# Ethernet.net
KiCad netlist of a schematic drawn in Altium Designer
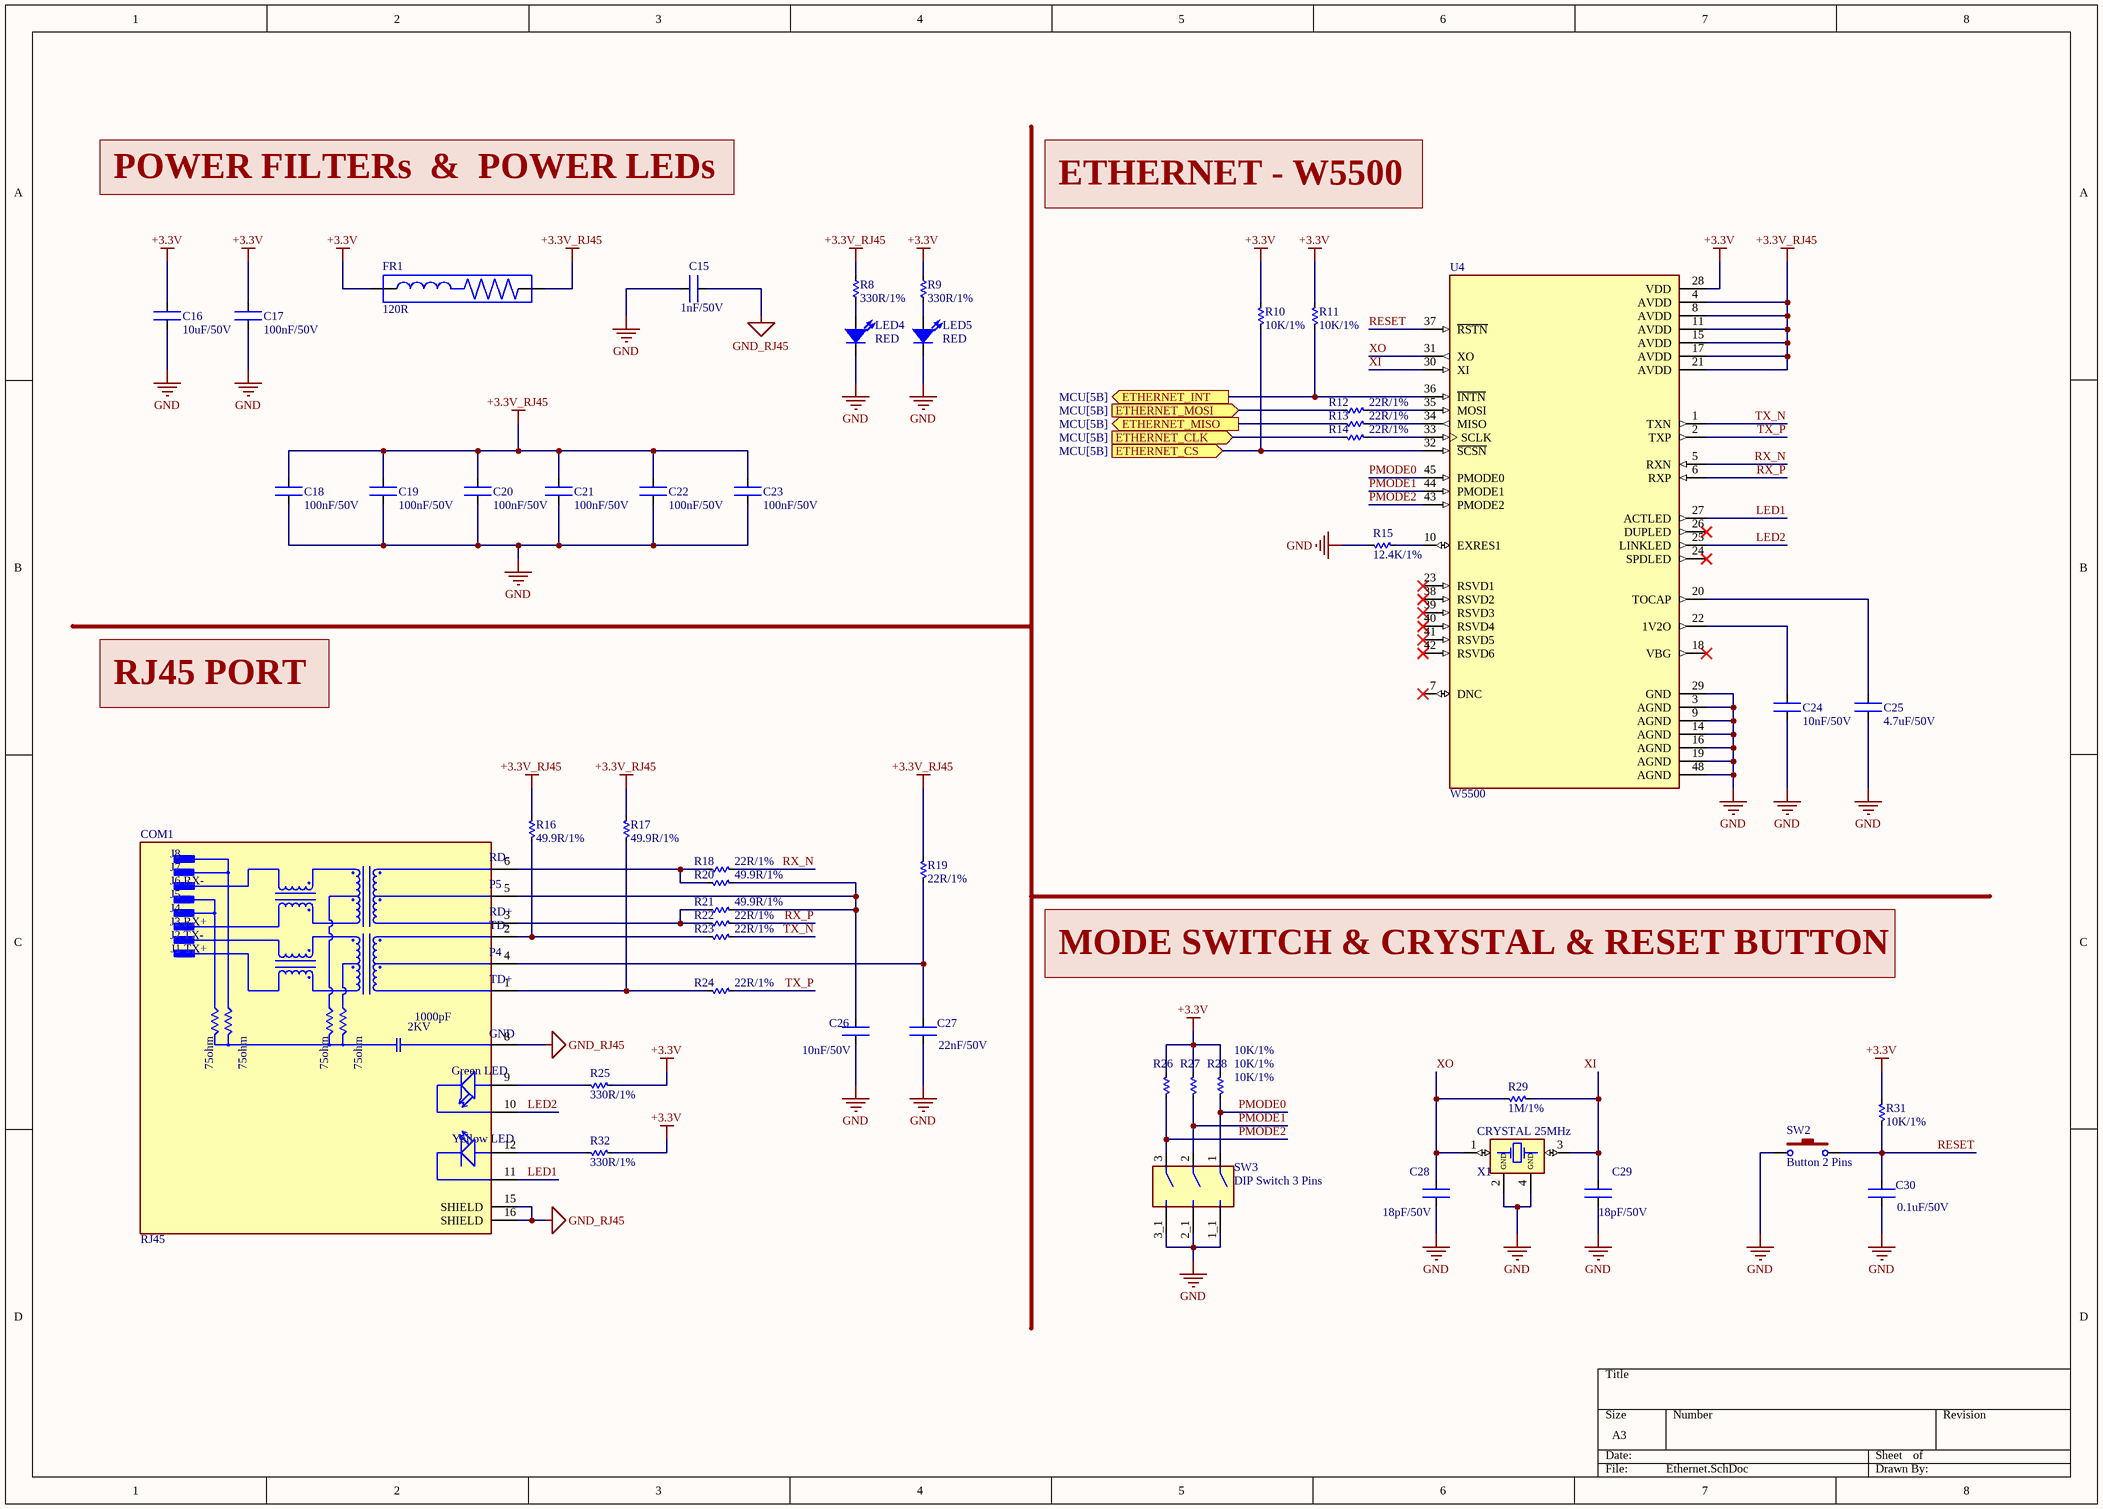
[diagram p0: Ethernet.SchDoc]

(export (version "E")
  (design (tool "Eeschema 10.0.6"))
  (components
    (comp (ref "C15")
      (value "1nF/50V")
      (footprint "CAP - 0603")
      (description "CAPACITOR SMD - KEMET")
      (libsource (lib "NewLibrary") (part "CAPACITOR"))
    )
    (comp (ref "C16")
      (value "10uF/50V")
      (footprint "CAP - 0603")
      (description "CAPACITOR SMD - KEMET")
      (libsource (lib "NewLibrary") (part "CAPACITOR"))
    )
    (comp (ref "C17")
      (value "100nF/50V")
      (footprint "CAP - 0603")
      (description "CAPACITOR SMD - KEMET")
      (libsource (lib "NewLibrary") (part "CAPACITOR"))
    )
    (comp (ref "C18")
      (value "100nF/50V")
      (footprint "CAP - 0603")
      (description "CAPACITOR SMD - KEMET")
      (libsource (lib "NewLibrary") (part "CAPACITOR"))
    )
    (comp (ref "C19")
      (value "100nF/50V")
      (footprint "CAP - 0603")
      (description "CAPACITOR SMD - KEMET")
      (libsource (lib "NewLibrary") (part "CAPACITOR"))
    )
    (comp (ref "C20")
      (value "100nF/50V")
      (footprint "CAP - 0603")
      (description "CAPACITOR SMD - KEMET")
      (libsource (lib "NewLibrary") (part "CAPACITOR"))
    )
    (comp (ref "C21")
      (value "100nF/50V")
      (footprint "CAP - 0603")
      (description "CAPACITOR SMD - KEMET")
      (libsource (lib "NewLibrary") (part "CAPACITOR"))
    )
    (comp (ref "C22")
      (value "100nF/50V")
      (footprint "CAP - 0603")
      (description "CAPACITOR SMD - KEMET")
      (libsource (lib "NewLibrary") (part "CAPACITOR"))
    )
    (comp (ref "C23")
      (value "100nF/50V")
      (footprint "CAP - 0603")
      (description "CAPACITOR SMD - KEMET")
      (libsource (lib "NewLibrary") (part "CAPACITOR"))
    )
    (comp (ref "C24")
      (value "10nF/50V")
      (footprint "CAP - 0603")
      (description "CAPACITOR SMD - KEMET")
      (libsource (lib "NewLibrary") (part "CAPACITOR"))
    )
    (comp (ref "C25")
      (value "4.7uF/50V")
      (footprint "CAP - 0603")
      (description "CAPACITOR SMD - KEMET")
      (libsource (lib "NewLibrary") (part "CAPACITOR"))
    )
    (comp (ref "C26")
      (value "10nF/50V")
      (footprint "CAP - 0603")
      (description "CAPACITOR SMD - KEMET")
      (libsource (lib "NewLibrary") (part "CAPACITOR"))
    )
    (comp (ref "C27")
      (value "22nF/50V")
      (footprint "CAP - 0603")
      (description "CAPACITOR SMD - KEMET")
      (libsource (lib "NewLibrary") (part "CAPACITOR"))
    )
    (comp (ref "C28")
      (value "18pF/50V")
      (footprint "CAP - 0603")
      (description "CAPACITOR SMD - KEMET")
      (libsource (lib "NewLibrary") (part "CAPACITOR"))
    )
    (comp (ref "C29")
      (value "18pF/50V")
      (footprint "CAP - 0603")
      (description "CAPACITOR SMD - KEMET")
      (libsource (lib "NewLibrary") (part "CAPACITOR"))
    )
    (comp (ref "C30")
      (value "0.1uF/50V")
      (footprint "CAP - 0603")
      (description "CAPACITOR SMD - KEMET")
      (libsource (lib "NewLibrary") (part "CAPACITOR"))
    )
    (comp (ref "COM1")
      (value "RJ45")
      (footprint "RJ45")
      (description "HR911105A")
      (libsource (lib "NewLibrary") (part "RJ45"))
    )
    (comp (ref "FR1")
      (value "120R")
      (footprint "FR-0805")
      (description "SMD")
      (libsource (lib "NewLibrary") (part "Ferrite Beads"))
    )
    (comp (ref "LED4")
      (value "RED")
      (footprint "RED_LED_0603")
      (description "LED SMD")
      (libsource (lib "NewLibrary") (part "LED_SMD"))
    )
    (comp (ref "LED5")
      (value "RED")
      (footprint "RED_LED_0603")
      (description "LED SMD")
      (libsource (lib "NewLibrary") (part "LED_SMD"))
    )
    (comp (ref "R8")
      (value "330R/1%")
      (footprint "RES - 0603")
      (description "Resistor SMD - YAGEO")
      (libsource (lib "NewLibrary") (part "RESISTOR"))
    )
    (comp (ref "R9")
      (value "330R/1%")
      (footprint "RES - 0603")
      (description "Resistor SMD - YAGEO")
      (libsource (lib "NewLibrary") (part "RESISTOR"))
    )
    (comp (ref "R10")
      (value "10K/1%")
      (footprint "RES - 0603")
      (description "Resistor SMD - YAGEO")
      (libsource (lib "NewLibrary") (part "RESISTOR"))
    )
    (comp (ref "R11")
      (value "10K/1%")
      (footprint "RES - 0603")
      (description "Resistor SMD - YAGEO")
      (libsource (lib "NewLibrary") (part "RESISTOR"))
    )
    (comp (ref "R12")
      (value "22R/1%")
      (footprint "RES - 0603")
      (description "Resistor SMD - YAGEO")
      (libsource (lib "NewLibrary") (part "RESISTOR"))
    )
    (comp (ref "R13")
      (value "22R/1%")
      (footprint "RES - 0603")
      (description "Resistor SMD - YAGEO")
      (libsource (lib "NewLibrary") (part "RESISTOR"))
    )
    (comp (ref "R14")
      (value "22R/1%")
      (footprint "RES - 0603")
      (description "Resistor SMD - YAGEO")
      (libsource (lib "NewLibrary") (part "RESISTOR"))
    )
    (comp (ref "R15")
      (value "12.4K/1%")
      (footprint "RES - 0603")
      (description "Resistor SMD - YAGEO")
      (libsource (lib "NewLibrary") (part "RESISTOR"))
    )
    (comp (ref "R16")
      (value "49.9R/1%")
      (footprint "RES - 0603")
      (description "Resistor SMD - YAGEO")
      (libsource (lib "NewLibrary") (part "RESISTOR"))
    )
    (comp (ref "R17")
      (value "49.9R/1%")
      (footprint "RES - 0603")
      (description "Resistor SMD - YAGEO")
      (libsource (lib "NewLibrary") (part "RESISTOR"))
    )
    (comp (ref "R18")
      (value "22R/1%")
      (footprint "RES - 0603")
      (description "Resistor SMD - YAGEO")
      (libsource (lib "NewLibrary") (part "RESISTOR"))
    )
    (comp (ref "R19")
      (value "22R/1%")
      (footprint "RES - 0603")
      (description "Resistor SMD - YAGEO")
      (libsource (lib "NewLibrary") (part "RESISTOR"))
    )
    (comp (ref "R20")
      (value "49.9R/1%")
      (footprint "RES - 0603")
      (description "Resistor SMD - YAGEO")
      (libsource (lib "NewLibrary") (part "RESISTOR"))
    )
    (comp (ref "R21")
      (value "49.9R/1%")
      (footprint "RES - 0603")
      (description "Resistor SMD - YAGEO")
      (libsource (lib "NewLibrary") (part "RESISTOR"))
    )
    (comp (ref "R22")
      (value "22R/1%")
      (footprint "RES - 0603")
      (description "Resistor SMD - YAGEO")
      (libsource (lib "NewLibrary") (part "RESISTOR"))
    )
    (comp (ref "R23")
      (value "22R/1%")
      (footprint "RES - 0603")
      (description "Resistor SMD - YAGEO")
      (libsource (lib "NewLibrary") (part "RESISTOR"))
    )
    (comp (ref "R24")
      (value "22R/1%")
      (footprint "RES - 0603")
      (description "Resistor SMD - YAGEO")
      (libsource (lib "NewLibrary") (part "RESISTOR"))
    )
    (comp (ref "R25")
      (value "330R/1%")
      (footprint "RES - 0603")
      (description "Resistor SMD - YAGEO")
      (libsource (lib "NewLibrary") (part "RESISTOR"))
    )
    (comp (ref "R26")
      (value "10K/1%")
      (footprint "RES - 0603")
      (description "Resistor SMD - YAGEO")
      (libsource (lib "NewLibrary") (part "RESISTOR"))
    )
    (comp (ref "R27")
      (value "10K/1%")
      (footprint "RES - 0603")
      (description "Resistor SMD - YAGEO")
      (libsource (lib "NewLibrary") (part "RESISTOR"))
    )
    (comp (ref "R28")
      (value "10K/1%")
      (footprint "RES - 0603")
      (description "Resistor SMD - YAGEO")
      (libsource (lib "NewLibrary") (part "RESISTOR"))
    )
    (comp (ref "R29")
      (value "1M/1%")
      (footprint "RES - 0603")
      (description "Resistor SMD - YAGEO")
      (libsource (lib "NewLibrary") (part "RESISTOR"))
    )
    (comp (ref "R31")
      (value "10K/1%")
      (footprint "RES - 0603")
      (description "Resistor SMD - YAGEO")
      (libsource (lib "NewLibrary") (part "RESISTOR"))
    )
    (comp (ref "R32")
      (value "330R/1%")
      (footprint "RES - 0603")
      (description "Resistor SMD - YAGEO")
      (libsource (lib "NewLibrary") (part "RESISTOR"))
    )
    (comp (ref "SW2")
      (value "Button 2 Pins")
      (footprint "SMD SWITCH 2 PINS")
      (description "SMD Button")
      (libsource (lib "NewLibrary") (part "Button 2 Pins"))
    )
    (comp (ref "SW3")
      (value "DIP Switch 3 Pins")
      (footprint "SMD - SW - 3Pins")
      (description "Switch DIP ON OFF SPST 3 Flush Slide 0.1A 20VDC Gull Wing 2000Cycles 2.54mm SMD T/R")
      (libsource (lib "NewLibrary") (part "DIP Switch 3 Pins"))
    )
    (comp (ref "U4")
      (value "W5500")
      (footprint "LQFP-48")
      (description "Hardwired TCP/IP embedded Ethernet controller")
      (libsource (lib "NewLibrary") (part "W5500"))
    )
    (comp (ref "X1")
      (value "CRYSTAL 25MHz")
      (footprint "crystal - 3.2 x 2.5 mm")
      (description "SMD CRYSTAL")
      (libsource (lib "NewLibrary") (part "CRYSTAL 8MHz"))
    )
  )
  (nets
    (net (code "1") (name "+3.3V") (class "Default")
      (node (ref "C16") (pin "2") (pinfunction "2_2") (pintype "passive"))
      (node (ref "C17") (pin "2") (pinfunction "2_2") (pintype "passive"))
      (node (ref "FR1") (pin "1") (pinfunction "1_1") (pintype "passive"))
      (node (ref "R10") (pin "2") (pinfunction "2_2") (pintype "passive"))
      (node (ref "R11") (pin "2") (pinfunction "2_2") (pintype "passive"))
      (node (ref "R25") (pin "1") (pinfunction "1_1") (pintype "passive"))
      (node (ref "R26") (pin "2") (pinfunction "2_2") (pintype "passive"))
      (node (ref "R27") (pin "2") (pinfunction "2_2") (pintype "passive"))
      (node (ref "R28") (pin "2") (pinfunction "2_2") (pintype "passive"))
      (node (ref "R31") (pin "1") (pinfunction "1_1") (pintype "passive"))
      (node (ref "R32") (pin "1") (pinfunction "1_1") (pintype "passive"))
      (node (ref "R9") (pin "1") (pinfunction "1_1") (pintype "passive"))
      (node (ref "U4") (pin "28") (pinfunction "VDD_28") (pintype "power_in"))
    )
    (net (code "2") (name "+3.3V_RJ45") (class "Default")
      (node (ref "C18") (pin "2") (pinfunction "2_2") (pintype "passive"))
      (node (ref "C19") (pin "2") (pinfunction "2_2") (pintype "passive"))
      (node (ref "C20") (pin "2") (pinfunction "2_2") (pintype "passive"))
      (node (ref "C21") (pin "2") (pinfunction "2_2") (pintype "passive"))
      (node (ref "C22") (pin "2") (pinfunction "2_2") (pintype "passive"))
      (node (ref "C23") (pin "2") (pinfunction "2_2") (pintype "passive"))
      (node (ref "FR1") (pin "2") (pinfunction "2_2") (pintype "passive"))
      (node (ref "R16") (pin "2") (pinfunction "2_2") (pintype "passive"))
      (node (ref "R17") (pin "2") (pinfunction "2_2") (pintype "passive"))
      (node (ref "R19") (pin "1") (pinfunction "1_1") (pintype "passive"))
      (node (ref "R8") (pin "1") (pinfunction "1_1") (pintype "passive"))
      (node (ref "U4") (pin "11") (pinfunction "AVDD_11") (pintype "power_in"))
      (node (ref "U4") (pin "15") (pinfunction "AVDD_15") (pintype "power_in"))
      (node (ref "U4") (pin "17") (pinfunction "AVDD_17") (pintype "power_in"))
      (node (ref "U4") (pin "21") (pinfunction "AVDD_21") (pintype "power_in"))
      (node (ref "U4") (pin "4") (pinfunction "AVDD_4") (pintype "power_in"))
      (node (ref "U4") (pin "8") (pinfunction "AVDD_8") (pintype "power_in"))
    )
    (net (code "3") (name "/ETHERNET_CLK") (class "Default")
      (node (ref "R14") (pin "2") (pinfunction "2_2") (pintype "passive"))
    )
    (net (code "4") (name "/ETHERNET_CS") (class "Default")
      (node (ref "R10") (pin "1") (pinfunction "1_1") (pintype "passive"))
      (node (ref "U4") (pin "32") (pinfunction "~{SCSN}_32") (pintype "input"))
    )
    (net (code "5") (name "/ETHERNET_INT") (class "Default")
      (node (ref "R11") (pin "1") (pinfunction "1_1") (pintype "passive"))
      (node (ref "U4") (pin "36") (pinfunction "~{INTN}_36") (pintype "input"))
    )
    (net (code "6") (name "/ETHERNET_MISO") (class "Default")
      (node (ref "R13") (pin "2") (pinfunction "2_2") (pintype "passive"))
    )
    (net (code "7") (name "/ETHERNET_MOSI") (class "Default")
      (node (ref "R12") (pin "2") (pinfunction "2_2") (pintype "passive"))
    )
    (net (code "8") (name "/LED1") (class "Default")
      (node (ref "COM1") (pin "11") (pinfunction "YC_11") (pintype "passive"))
      (node (ref "U4") (pin "27") (pinfunction "ACTLED_27") (pintype "output"))
    )
    (net (code "9") (name "/LED2") (class "Default")
      (node (ref "COM1") (pin "10") (pinfunction "GC_10") (pintype "passive"))
      (node (ref "U4") (pin "25") (pinfunction "LINKLED_25") (pintype "output"))
    )
    (net (code "10") (name "/PMODE0") (class "Default")
      (node (ref "R28") (pin "1") (pinfunction "1_1") (pintype "passive"))
      (node (ref "SW3") (pin "1") (pinfunction "1_1") (pintype "passive"))
      (node (ref "U4") (pin "45") (pinfunction "PMODE0_45") (pintype "input"))
    )
    (net (code "11") (name "/PMODE1") (class "Default")
      (node (ref "R27") (pin "1") (pinfunction "1_1") (pintype "passive"))
      (node (ref "SW3") (pin "2") (pinfunction "2_2") (pintype "passive"))
      (node (ref "U4") (pin "44") (pinfunction "PMODE1_44") (pintype "input"))
    )
    (net (code "12") (name "/PMODE2") (class "Default")
      (node (ref "R26") (pin "1") (pinfunction "1_1") (pintype "passive"))
      (node (ref "SW3") (pin "3") (pinfunction "3_3") (pintype "passive"))
      (node (ref "U4") (pin "43") (pinfunction "PMODE2_43") (pintype "input"))
    )
    (net (code "13") (name "/RESET") (class "Default")
      (node (ref "C30") (pin "2") (pinfunction "2_2") (pintype "passive"))
      (node (ref "R31") (pin "2") (pinfunction "2_2") (pintype "passive"))
      (node (ref "SW2") (pin "2") (pinfunction "2_2") (pintype "passive"))
      (node (ref "U4") (pin "37") (pinfunction "~{RSTN}_37") (pintype "input"))
    )
    (net (code "14") (name "/RX_N") (class "Default")
      (node (ref "R18") (pin "1") (pinfunction "1_1") (pintype "passive"))
      (node (ref "U4") (pin "5") (pinfunction "RXN_5") (pintype "input"))
    )
    (net (code "15") (name "/RX_P") (class "Default")
      (node (ref "R22") (pin "1") (pinfunction "1_1") (pintype "passive"))
      (node (ref "U4") (pin "6") (pinfunction "RXP_6") (pintype "input"))
    )
    (net (code "16") (name "/TX_N") (class "Default")
      (node (ref "R23") (pin "1") (pinfunction "1_1") (pintype "passive"))
      (node (ref "U4") (pin "1") (pinfunction "TXN_1") (pintype "output"))
    )
    (net (code "17") (name "/TX_P") (class "Default")
      (node (ref "R24") (pin "1") (pinfunction "1_1") (pintype "passive"))
      (node (ref "U4") (pin "2") (pinfunction "TXP_2") (pintype "output"))
    )
    (net (code "18") (name "/XI") (class "Default")
      (node (ref "C29") (pin "2") (pinfunction "2_2") (pintype "passive"))
      (node (ref "R29") (pin "1") (pinfunction "1_1") (pintype "passive"))
      (node (ref "U4") (pin "30") (pinfunction "XI_30") (pintype "input"))
      (node (ref "X1") (pin "3") (pinfunction "OUT/IN_3") (pintype "bidirectional"))
    )
    (net (code "19") (name "/XO") (class "Default")
      (node (ref "C28") (pin "2") (pinfunction "2_2") (pintype "passive"))
      (node (ref "R29") (pin "2") (pinfunction "2_2") (pintype "passive"))
      (node (ref "U4") (pin "31") (pinfunction "XO_31") (pintype "output"))
      (node (ref "X1") (pin "1") (pinfunction "IN/OUT_1") (pintype "bidirectional"))
    )
    (net (code "20") (name "GND") (class "Default")
      (node (ref "C15") (pin "1") (pinfunction "1_1") (pintype "passive"))
      (node (ref "C16") (pin "1") (pinfunction "1_1") (pintype "passive"))
      (node (ref "C17") (pin "1") (pinfunction "1_1") (pintype "passive"))
      (node (ref "C18") (pin "1") (pinfunction "1_1") (pintype "passive"))
      (node (ref "C19") (pin "1") (pinfunction "1_1") (pintype "passive"))
      (node (ref "C20") (pin "1") (pinfunction "1_1") (pintype "passive"))
      (node (ref "C21") (pin "1") (pinfunction "1_1") (pintype "passive"))
      (node (ref "C22") (pin "1") (pinfunction "1_1") (pintype "passive"))
      (node (ref "C23") (pin "1") (pinfunction "1_1") (pintype "passive"))
      (node (ref "C24") (pin "1") (pinfunction "1_1") (pintype "passive"))
      (node (ref "C25") (pin "1") (pinfunction "1_1") (pintype "passive"))
      (node (ref "C26") (pin "1") (pinfunction "1_1") (pintype "passive"))
      (node (ref "C27") (pin "1") (pinfunction "1_1") (pintype "passive"))
      (node (ref "C28") (pin "1") (pinfunction "1_1") (pintype "passive"))
      (node (ref "C29") (pin "1") (pinfunction "1_1") (pintype "passive"))
      (node (ref "C30") (pin "1") (pinfunction "1_1") (pintype "passive"))
      (node (ref "LED4") (pin "2") (pinfunction "2_2") (pintype "passive"))
      (node (ref "LED5") (pin "2") (pinfunction "2_2") (pintype "passive"))
      (node (ref "R15") (pin "1") (pinfunction "1_1") (pintype "passive"))
      (node (ref "SW2") (pin "1") (pinfunction "1_1") (pintype "passive"))
      (node (ref "SW3") (pin "1_1") (pinfunction "1_1_1_1") (pintype "passive"))
      (node (ref "SW3") (pin "2_1") (pinfunction "2_1_2_1") (pintype "passive"))
      (node (ref "SW3") (pin "3_1") (pinfunction "3_1_3_1") (pintype "passive"))
      (node (ref "U4") (pin "14") (pinfunction "AGND_14") (pintype "power_in"))
      (node (ref "U4") (pin "16") (pinfunction "AGND_16") (pintype "power_in"))
      (node (ref "U4") (pin "19") (pinfunction "AGND_19") (pintype "power_in"))
      (node (ref "U4") (pin "29") (pinfunction "GND_29") (pintype "passive"))
      (node (ref "U4") (pin "3") (pinfunction "AGND_3") (pintype "power_in"))
      (node (ref "U4") (pin "48") (pinfunction "AGND_48") (pintype "power_in"))
      (node (ref "U4") (pin "9") (pinfunction "AGND_9") (pintype "power_in"))
      (node (ref "X1") (pin "2") (pinfunction "GND_2") (pintype "power_in"))
      (node (ref "X1") (pin "4") (pinfunction "GND_4") (pintype "power_in"))
    )
    (net (code "21") (name "GND_RJ45") (class "Default")
      (node (ref "C15") (pin "2") (pinfunction "2_2") (pintype "passive"))
      (node (ref "COM1") (pin "15") (pinfunction "SHIELD_15") (pintype "passive"))
      (node (ref "COM1") (pin "16") (pinfunction "SHIELD_16") (pintype "passive"))
      (node (ref "COM1") (pin "8") (pinfunction "GND_8") (pintype "power_in"))
    )
    (net (code "22") (name "Net-(COM1-GA)") (class "Default")
      (node (ref "COM1") (pin "9") (pinfunction "GA_9") (pintype "passive"))
      (node (ref "R25") (pin "2") (pinfunction "2_2") (pintype "passive"))
    )
    (net (code "23") (name "Net-(COM1-P4)") (class "Default")
      (node (ref "C27") (pin "2") (pinfunction "2_2") (pintype "passive"))
      (node (ref "COM1") (pin "4") (pinfunction "P4_4") (pintype "passive"))
      (node (ref "R19") (pin "2") (pinfunction "2_2") (pintype "passive"))
    )
    (net (code "24") (name "Net-(COM1-P5)") (class "Default")
      (node (ref "C26") (pin "2") (pinfunction "2_2") (pintype "passive"))
      (node (ref "COM1") (pin "5") (pinfunction "P5_5") (pintype "passive"))
      (node (ref "R20") (pin "1") (pinfunction "1_1") (pintype "passive"))
      (node (ref "R21") (pin "1") (pinfunction "1_1") (pintype "passive"))
    )
    (net (code "25") (name "Net-(COM1-RD+)") (class "Default")
      (node (ref "COM1") (pin "3") (pinfunction "RD+_3") (pintype "passive"))
      (node (ref "R21") (pin "2") (pinfunction "2_2") (pintype "passive"))
      (node (ref "R22") (pin "2") (pinfunction "2_2") (pintype "passive"))
    )
    (net (code "26") (name "Net-(COM1-RD-)") (class "Default")
      (node (ref "COM1") (pin "6") (pinfunction "RD-_6") (pintype "passive"))
      (node (ref "R18") (pin "2") (pinfunction "2_2") (pintype "passive"))
      (node (ref "R20") (pin "2") (pinfunction "2_2") (pintype "passive"))
    )
    (net (code "27") (name "Net-(COM1-TD+)") (class "Default")
      (node (ref "COM1") (pin "1") (pinfunction "TD+_1") (pintype "passive"))
      (node (ref "R17") (pin "1") (pinfunction "1_1") (pintype "passive"))
      (node (ref "R24") (pin "2") (pinfunction "2_2") (pintype "passive"))
    )
    (net (code "28") (name "Net-(COM1-TD-)") (class "Default")
      (node (ref "COM1") (pin "2") (pinfunction "TD-_2") (pintype "passive"))
      (node (ref "R16") (pin "1") (pinfunction "1_1") (pintype "passive"))
      (node (ref "R23") (pin "2") (pinfunction "2_2") (pintype "passive"))
    )
    (net (code "29") (name "Net-(COM1-YA)") (class "Default")
      (node (ref "COM1") (pin "12") (pinfunction "YA_12") (pintype "passive"))
      (node (ref "R32") (pin "2") (pinfunction "2_2") (pintype "passive"))
    )
    (net (code "30") (name "Net-(LED4-Pad1)") (class "Default")
      (node (ref "LED4") (pin "1") (pinfunction "1_1") (pintype "passive"))
      (node (ref "R8") (pin "2") (pinfunction "2_2") (pintype "passive"))
    )
    (net (code "31") (name "Net-(LED5-Pad1)") (class "Default")
      (node (ref "LED5") (pin "1") (pinfunction "1_1") (pintype "passive"))
      (node (ref "R9") (pin "2") (pinfunction "2_2") (pintype "passive"))
    )
    (net (code "32") (name "Net-(U4-1V2O)") (class "Default")
      (node (ref "C24") (pin "2") (pinfunction "2_2") (pintype "passive"))
      (node (ref "U4") (pin "22") (pinfunction "1V2O_22") (pintype "output"))
    )
    (net (code "33") (name "Net-(U4-EXRES1)") (class "Default")
      (node (ref "R15") (pin "2") (pinfunction "2_2") (pintype "passive"))
      (node (ref "U4") (pin "10") (pinfunction "EXRES1_10") (pintype "bidirectional"))
    )
    (net (code "34") (name "Net-(U4-MISO)") (class "Default")
      (node (ref "R13") (pin "1") (pinfunction "1_1") (pintype "passive"))
      (node (ref "U4") (pin "34") (pinfunction "MISO_34") (pintype "output"))
    )
    (net (code "35") (name "Net-(U4-MOSI)") (class "Default")
      (node (ref "R12") (pin "1") (pinfunction "1_1") (pintype "passive"))
      (node (ref "U4") (pin "35") (pinfunction "MOSI_35") (pintype "input"))
    )
    (net (code "36") (name "Net-(U4-SCLK)") (class "Default")
      (node (ref "R14") (pin "1") (pinfunction "1_1") (pintype "passive"))
      (node (ref "U4") (pin "33") (pinfunction "SCLK_33") (pintype "input"))
    )
    (net (code "37") (name "Net-(U4-TOCAP)") (class "Default")
      (node (ref "C25") (pin "2") (pinfunction "2_2") (pintype "passive"))
      (node (ref "U4") (pin "20") (pinfunction "TOCAP_20") (pintype "output"))
    )
    (net (code "38") (name "unconnected-(U4-DNC-Pad7)") (class "Default")
      (node (ref "U4") (pin "7") (pinfunction "DNC_7") (pintype "bidirectional+no_connect"))
    )
    (net (code "39") (name "unconnected-(U4-DUPLED-Pad26)") (class "Default")
      (node (ref "U4") (pin "26") (pinfunction "DUPLED_26") (pintype "output+no_connect"))
    )
    (net (code "40") (name "unconnected-(U4-RSVD1-Pad23)") (class "Default")
      (node (ref "U4") (pin "23") (pinfunction "RSVD1_23") (pintype "input+no_connect"))
    )
    (net (code "41") (name "unconnected-(U4-RSVD2-Pad38)") (class "Default")
      (node (ref "U4") (pin "38") (pinfunction "RSVD2_38") (pintype "input+no_connect"))
    )
    (net (code "42") (name "unconnected-(U4-RSVD3-Pad39)") (class "Default")
      (node (ref "U4") (pin "39") (pinfunction "RSVD3_39") (pintype "input+no_connect"))
    )
    (net (code "43") (name "unconnected-(U4-RSVD4-Pad40)") (class "Default")
      (node (ref "U4") (pin "40") (pinfunction "RSVD4_40") (pintype "input+no_connect"))
    )
    (net (code "44") (name "unconnected-(U4-RSVD5-Pad41)") (class "Default")
      (node (ref "U4") (pin "41") (pinfunction "RSVD5_41") (pintype "input+no_connect"))
    )
    (net (code "45") (name "unconnected-(U4-RSVD6-Pad42)") (class "Default")
      (node (ref "U4") (pin "42") (pinfunction "RSVD6_42") (pintype "input+no_connect"))
    )
    (net (code "46") (name "unconnected-(U4-SPDLED-Pad24)") (class "Default")
      (node (ref "U4") (pin "24") (pinfunction "SPDLED_24") (pintype "output+no_connect"))
    )
    (net (code "47") (name "unconnected-(U4-VBG-Pad18)") (class "Default")
      (node (ref "U4") (pin "18") (pinfunction "VBG_18") (pintype "output+no_connect"))
    )
  )
)
